# Uebungsboard2017.net
KiCad netlist of a schematic drawn in EAGLE
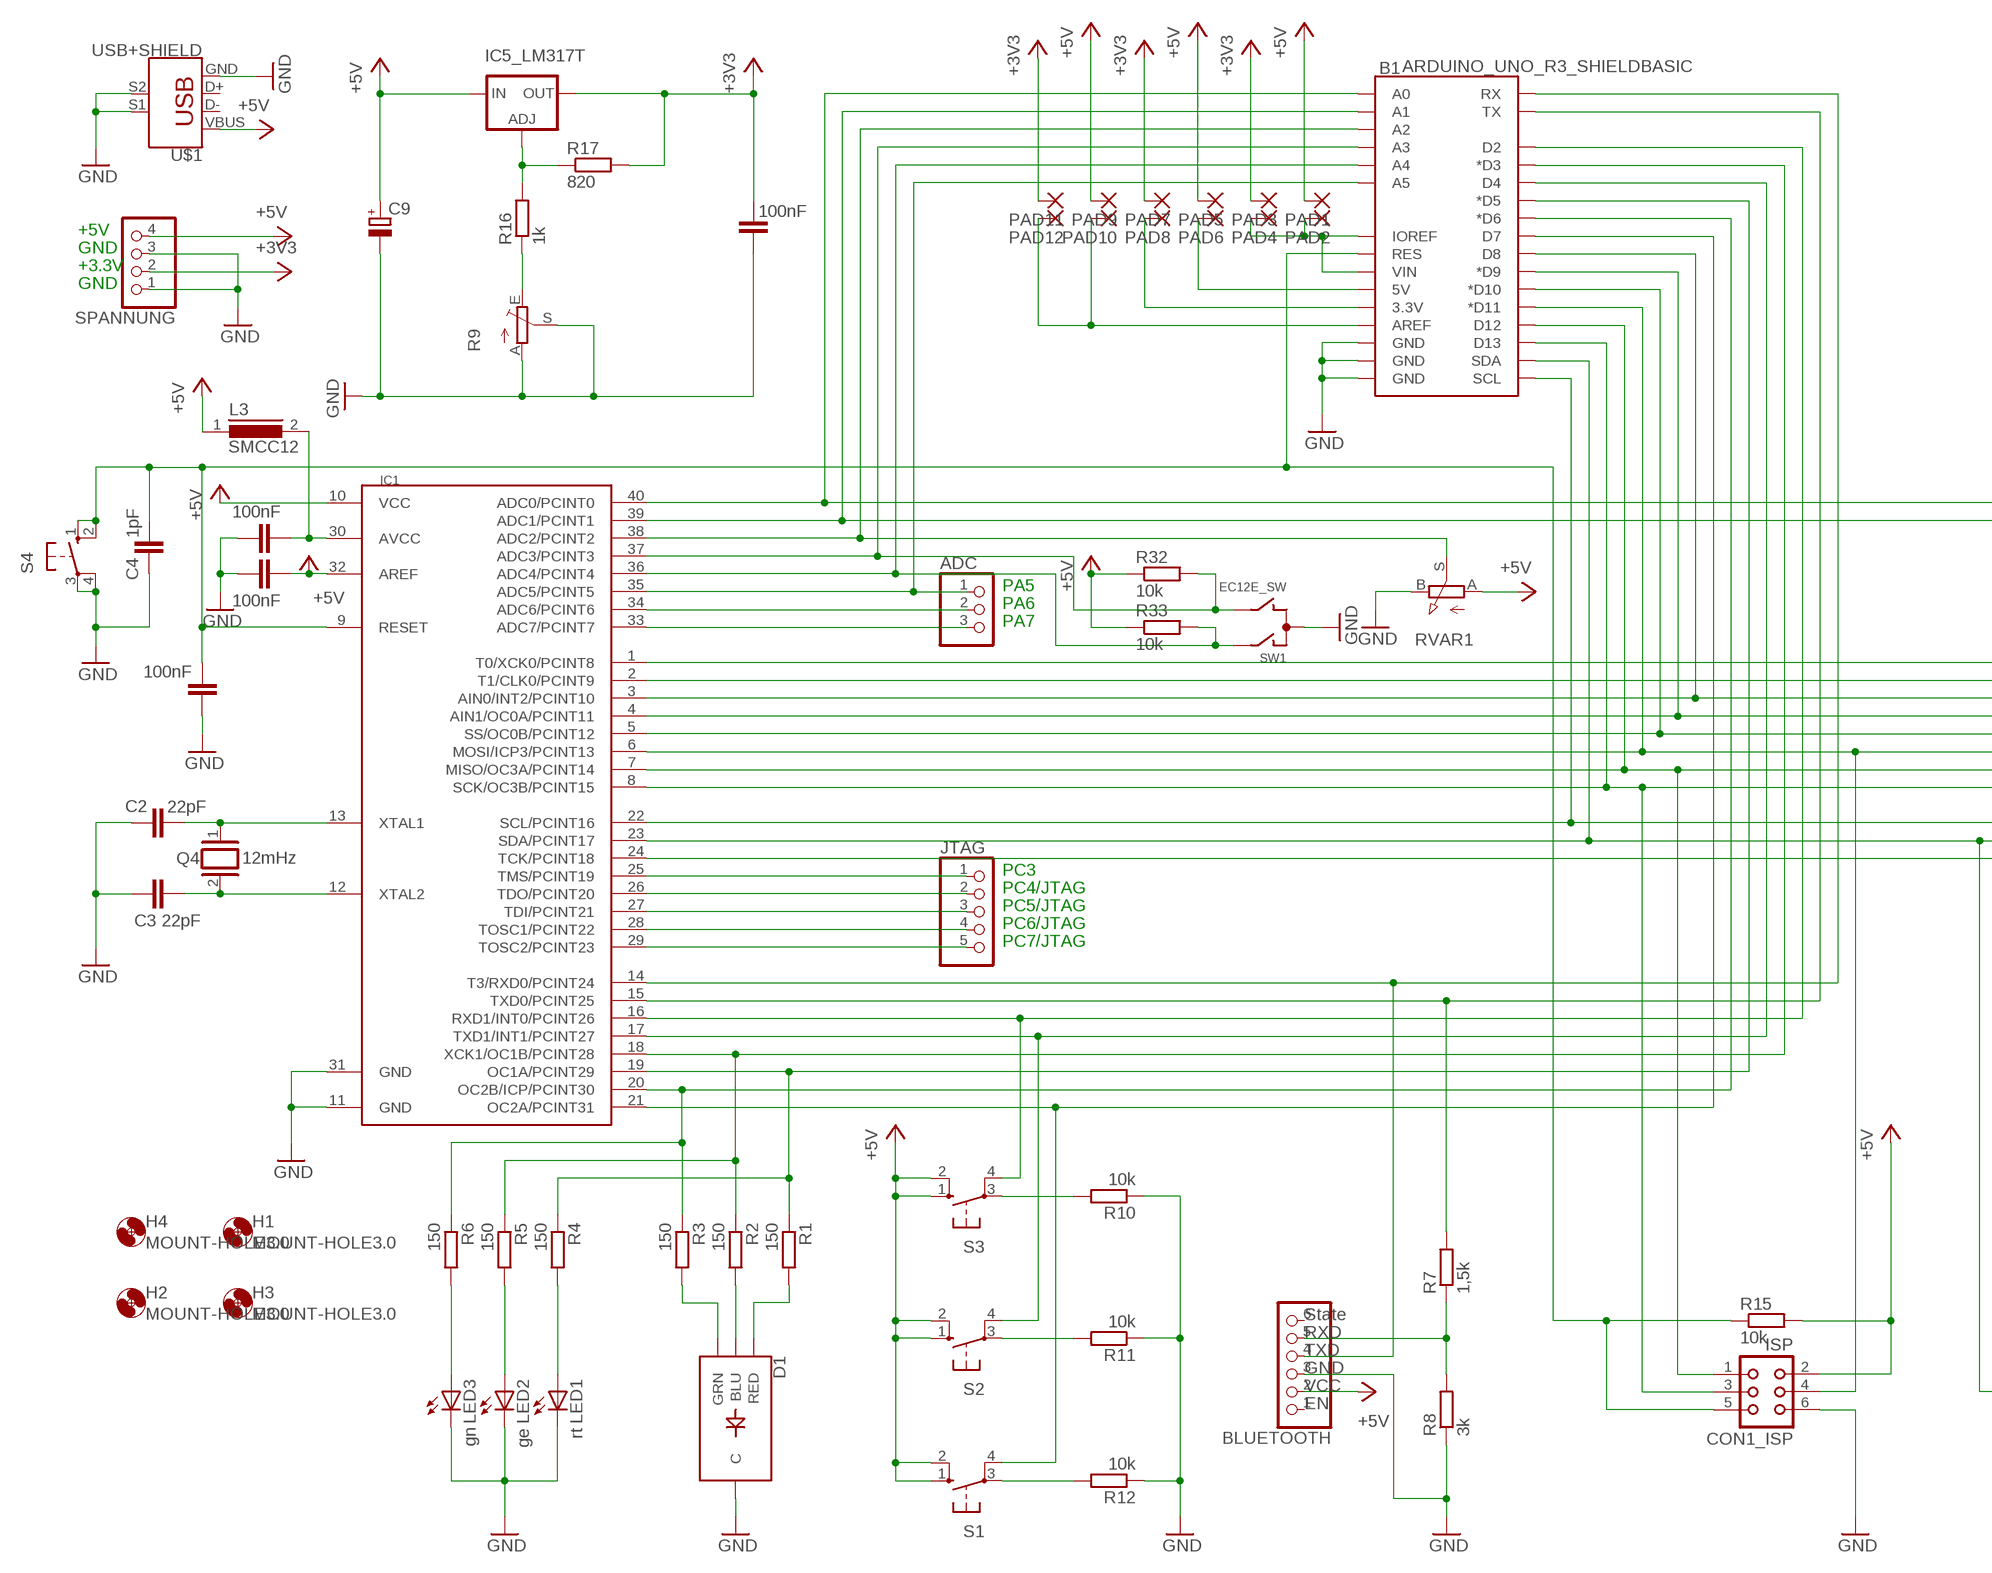
[diagram p0: schematic, sheet 1, part 1 of 2]
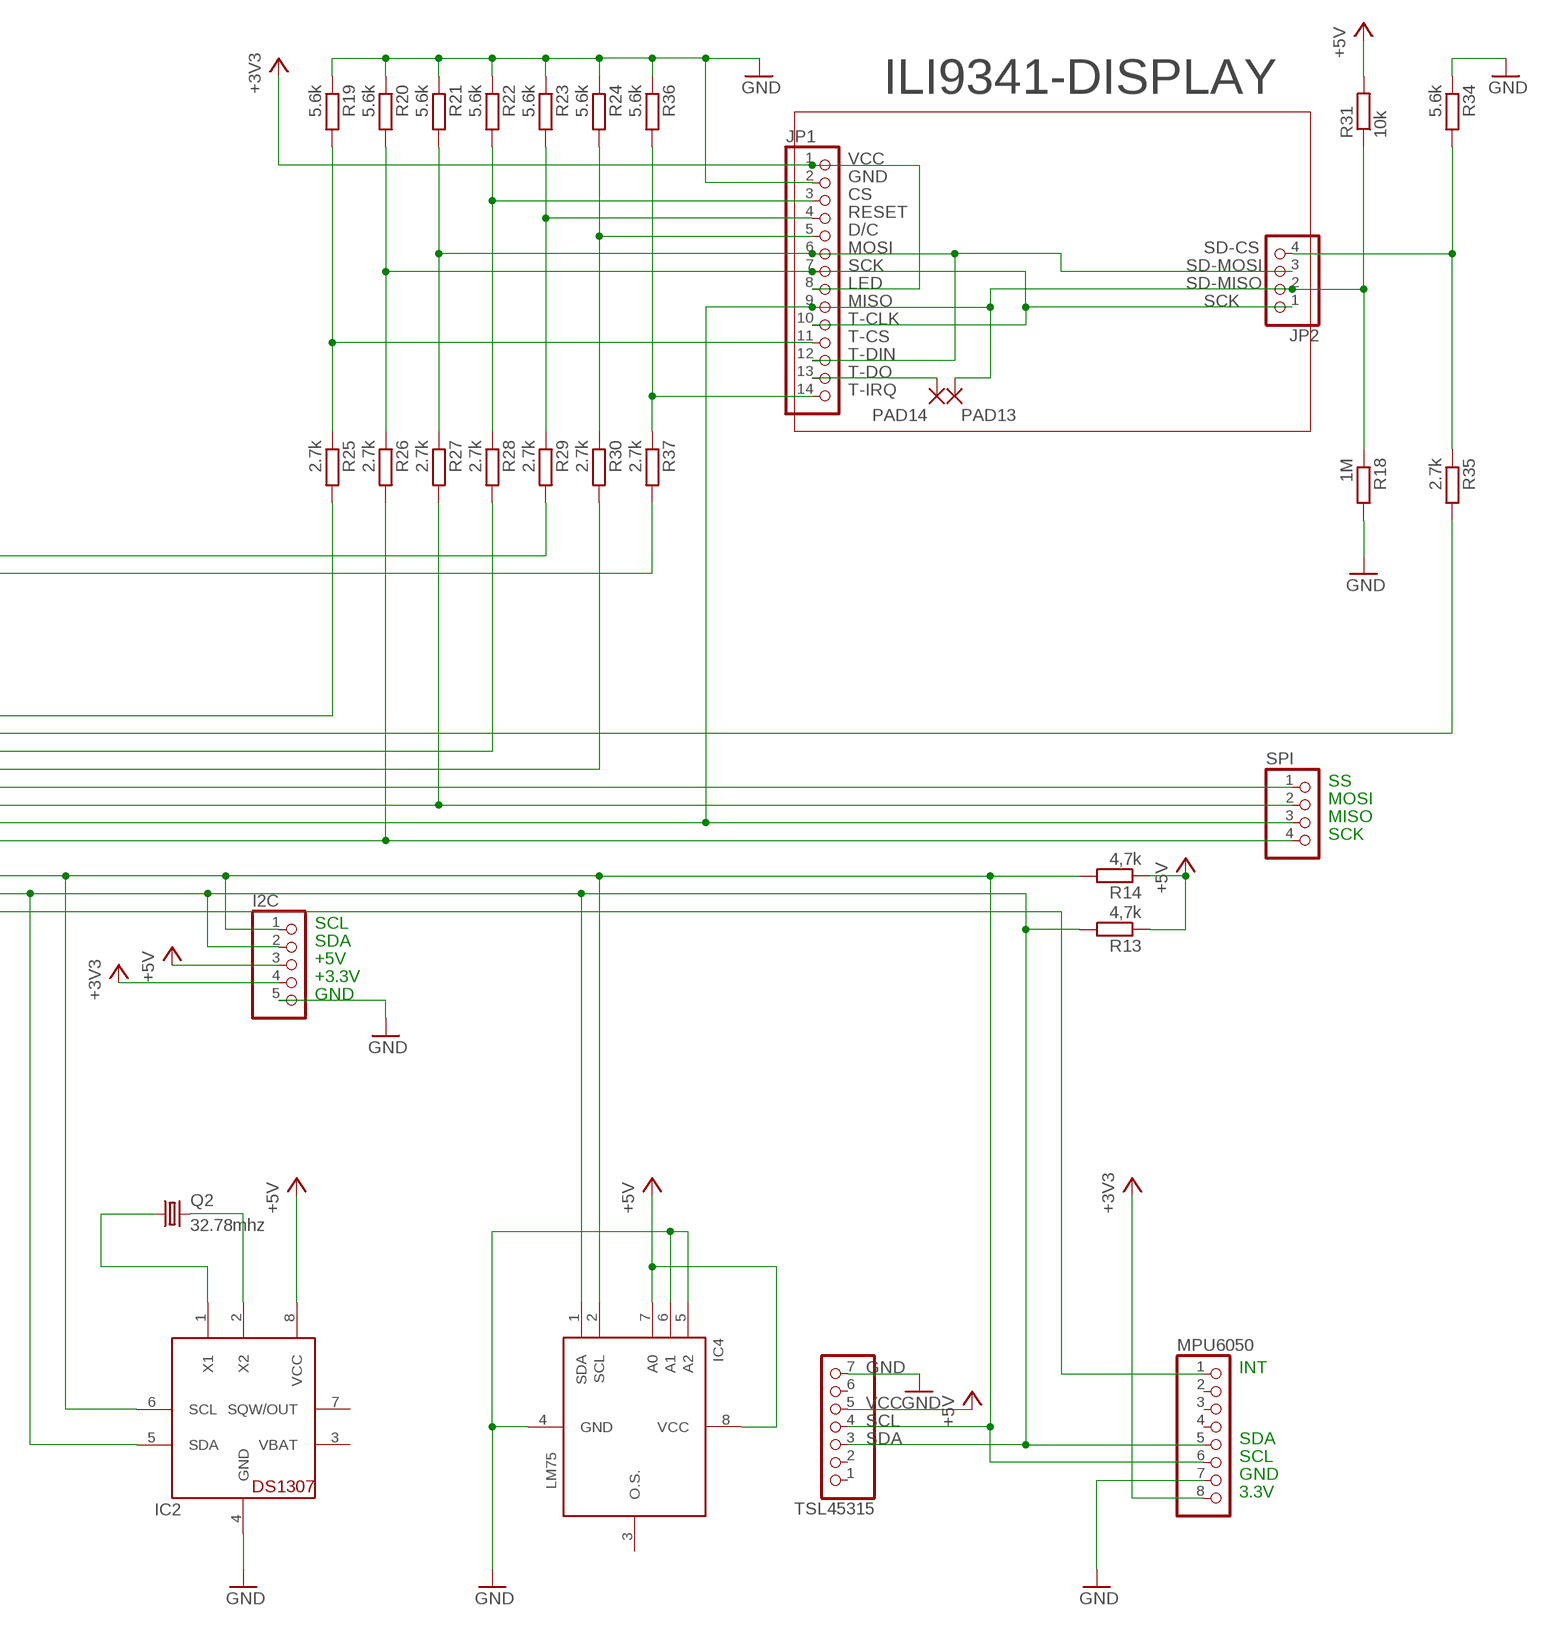
[diagram p1: schematic, sheet 1, part 2 of 2]

(export (version "E")
  (design (tool "Eeschema 10.0.6"))
  (components
    (comp (ref "ADC")
      (value "PINHD-1X3")
      (footprint "eagle-import:1X03")
      (libsource (lib "eagle-import") (part "PINHD-1X3"))
    )
    (comp (ref "B1")
      (value "ARDUINO_UNO_R3_SHIELDBASIC")
      (footprint "eagle-import:UNO_R3_SHIELD")
      (libsource (lib "eagle-import") (part "ARDUINO_UNO_R3_SHIELDBASIC"))
    )
    (comp (ref "BLUETOOTH")
      (value "PINHD-1X6")
      (footprint "eagle-import:1X06")
      (libsource (lib "eagle-import") (part "PINHD-1X6"))
    )
    (comp (ref "C2")
      (value "22pF")
      (footprint "eagle-import:C5B2.5")
      (libsource (lib "eagle-import") (part "C5/2.5"))
    )
    (comp (ref "C3")
      (value "22pF")
      (footprint "eagle-import:C5B2.5")
      (libsource (lib "eagle-import") (part "C5/2.5"))
    )
    (comp (ref "C4")
      (value "1pF")
      (footprint "eagle-import:C5B2.5")
      (libsource (lib "eagle-import") (part "C5/2.5"))
    )
    (comp (ref "C5")
      (value "100nF")
      (footprint "eagle-import:C5B2.5")
      (libsource (lib "eagle-import") (part "C5/2.5"))
    )
    (comp (ref "C6")
      (value "100nF")
      (footprint "eagle-import:C5B2.5")
      (libsource (lib "eagle-import") (part "C5/2.5"))
    )
    (comp (ref "C7")
      (value "100nF")
      (footprint "eagle-import:C5B2.5")
      (libsource (lib "eagle-import") (part "C5/2.5"))
    )
    (comp (ref "C8")
      (value "100nF")
      (footprint "eagle-import:C5B2.5")
      (libsource (lib "eagle-import") (part "C5/2.5"))
    )
    (comp (ref "C9")
      (value "CPOL-EUE2-5")
      (footprint "eagle-import:E2-5")
      (libsource (lib "eagle-import") (part "CPOL-EUE2-5"))
    )
    (comp (ref "CON1_ISP")
      (value "ISP")
      (footprint "eagle-import:CON06")
      (libsource (lib "eagle-import") (part "CON06"))
    )
    (comp (ref "D1")
      (value "LED-RGB-CCTEST")
      (footprint "eagle-import:LED-RGB-THRU")
      (libsource (lib "eagle-import") (part "LED-RGB-CCTEST"))
    )
    (comp (ref "H1")
      (value "MOUNT-HOLE3.0")
      (footprint "eagle-import:3,0")
      (libsource (lib "eagle-import") (part "MOUNT-HOLE3.0"))
    )
    (comp (ref "H2")
      (value "MOUNT-HOLE3.0")
      (footprint "eagle-import:3,0")
      (libsource (lib "eagle-import") (part "MOUNT-HOLE3.0"))
    )
    (comp (ref "H3")
      (value "MOUNT-HOLE3.0")
      (footprint "eagle-import:3,0")
      (libsource (lib "eagle-import") (part "MOUNT-HOLE3.0"))
    )
    (comp (ref "H4")
      (value "MOUNT-HOLE3.0")
      (footprint "eagle-import:3,0")
      (libsource (lib "eagle-import") (part "MOUNT-HOLE3.0"))
    )
    (comp (ref "I2C")
      (value "PINHD-1X5")
      (footprint "eagle-import:1X05")
      (libsource (lib "eagle-import") (part "PINHD-1X5"))
    )
    (comp (ref "IC1")
      (value "MEGA1284P")
      (footprint "eagle-import:DIL40")
      (libsource (lib "eagle-import") (part "MEGA1284P"))
    )
    (comp (ref "IC2")
      (value "DS1307")
      (footprint "eagle-import:DIL08")
      (libsource (lib "eagle-import") (part "DS1307"))
    )
    (comp (ref "IC4")
      (value "DS1721S")
      (footprint "eagle-import:SO-8")
      (libsource (lib "eagle-import") (part "DS1721S"))
    )
    (comp (ref "IC5_LM317T")
      (value "3.3V")
      (footprint "eagle-import:317TS")
      (libsource (lib "eagle-import") (part "LM317TS"))
    )
    (comp (ref "JP1")
      (value "PINHD-1X14")
      (footprint "eagle-import:1X14")
      (libsource (lib "eagle-import") (part "PINHD-1X14"))
    )
    (comp (ref "JP2")
      (value "PINHD-1X4")
      (footprint "eagle-import:1X04")
      (libsource (lib "eagle-import") (part "PINHD-1X4"))
    )
    (comp (ref "JTAG")
      (value "PINHD-1X5")
      (footprint "eagle-import:1X05")
      (libsource (lib "eagle-import") (part "PINHD-1X5"))
    )
    (comp (ref "L3")
      (value "SMCC12")
      (footprint "eagle-import:SMCC12")
      (libsource (lib "eagle-import") (part "SMCC12"))
    )
    (comp (ref "LED1")
      (value "rt")
      (footprint "eagle-import:LED5MM")
      (libsource (lib "eagle-import") (part "LED5MM"))
    )
    (comp (ref "LED2")
      (value "ge")
      (footprint "eagle-import:LED5MM")
      (libsource (lib "eagle-import") (part "LED5MM"))
    )
    (comp (ref "LED3")
      (value "gn")
      (footprint "eagle-import:LED5MM")
      (libsource (lib "eagle-import") (part "LED5MM"))
    )
    (comp (ref "MPU6050")
      (value "PINHD-1X8")
      (footprint "eagle-import:1X08")
      (libsource (lib "eagle-import") (part "PINHD-1X8"))
    )
    (comp (ref "PAD1")
      (value "1,6/0,8")
      (footprint "eagle-import:1,6_0,8")
      (libsource (lib "eagle-import") (part "1,6/0,8"))
    )
    (comp (ref "PAD2")
      (value "1,6/0,8")
      (footprint "eagle-import:1,6_0,8")
      (libsource (lib "eagle-import") (part "1,6/0,8"))
    )
    (comp (ref "PAD3")
      (value "1,6/0,8")
      (footprint "eagle-import:1,6_0,8")
      (libsource (lib "eagle-import") (part "1,6/0,8"))
    )
    (comp (ref "PAD4")
      (value "1,6/0,8")
      (footprint "eagle-import:1,6_0,8")
      (libsource (lib "eagle-import") (part "1,6/0,8"))
    )
    (comp (ref "PAD5")
      (value "1,6/0,8")
      (footprint "eagle-import:1,6_0,8")
      (libsource (lib "eagle-import") (part "1,6/0,8"))
    )
    (comp (ref "PAD6")
      (value "1,6/0,8")
      (footprint "eagle-import:1,6_0,8")
      (libsource (lib "eagle-import") (part "1,6/0,8"))
    )
    (comp (ref "PAD7")
      (value "1,6/0,8")
      (footprint "eagle-import:1,6_0,8")
      (libsource (lib "eagle-import") (part "1,6/0,8"))
    )
    (comp (ref "PAD8")
      (value "1,6/0,8")
      (footprint "eagle-import:1,6_0,8")
      (libsource (lib "eagle-import") (part "1,6/0,8"))
    )
    (comp (ref "PAD9")
      (value "1,6/0,8")
      (footprint "eagle-import:1,6_0,8")
      (libsource (lib "eagle-import") (part "1,6/0,8"))
    )
    (comp (ref "PAD10")
      (value "1,6/0,8")
      (footprint "eagle-import:1,6_0,8")
      (libsource (lib "eagle-import") (part "1,6/0,8"))
    )
    (comp (ref "PAD11")
      (value "1,6/0,8")
      (footprint "eagle-import:1,6_0,8")
      (libsource (lib "eagle-import") (part "1,6/0,8"))
    )
    (comp (ref "PAD12")
      (value "1,6/0,8")
      (footprint "eagle-import:1,6_0,8")
      (libsource (lib "eagle-import") (part "1,6/0,8"))
    )
    (comp (ref "PAD13")
      (value "1,6/0,8")
      (footprint "eagle-import:1,6_0,8")
      (libsource (lib "eagle-import") (part "1,6/0,8"))
    )
    (comp (ref "PAD14")
      (value "1,6/0,8")
      (footprint "eagle-import:1,6_0,8")
      (libsource (lib "eagle-import") (part "1,6/0,8"))
    )
    (comp (ref "Q2")
      (value "32.78mhz")
      (footprint "eagle-import:TC26H")
      (libsource (lib "eagle-import") (part "CRYSTALTC26H"))
    )
    (comp (ref "Q4")
      (value "12mHz")
      (footprint "eagle-import:QS")
      (libsource (lib "eagle-import") (part "XTAL/S"))
    )
    (comp (ref "R1")
      (value "150")
      (footprint "eagle-import:0207_10")
      (libsource (lib "eagle-import") (part "R-EU_0207/10"))
    )
    (comp (ref "R2")
      (value "150")
      (footprint "eagle-import:0207_10")
      (libsource (lib "eagle-import") (part "R-EU_0207/10"))
    )
    (comp (ref "R3")
      (value "150")
      (footprint "eagle-import:0207_10")
      (libsource (lib "eagle-import") (part "R-EU_0207/10"))
    )
    (comp (ref "R4")
      (value "150")
      (footprint "eagle-import:0207_10")
      (libsource (lib "eagle-import") (part "R-EU_0207/10"))
    )
    (comp (ref "R5")
      (value "150")
      (footprint "eagle-import:0207_10")
      (libsource (lib "eagle-import") (part "R-EU_0207/10"))
    )
    (comp (ref "R6")
      (value "150")
      (footprint "eagle-import:0207_10")
      (libsource (lib "eagle-import") (part "R-EU_0207/10"))
    )
    (comp (ref "R7")
      (value "1,5k")
      (footprint "eagle-import:0207_10")
      (libsource (lib "eagle-import") (part "R-EU_0207/10"))
    )
    (comp (ref "R8")
      (value "3k")
      (footprint "eagle-import:0207_10")
      (libsource (lib "eagle-import") (part "R-EU_0207/10"))
    )
    (comp (ref "R9")
      (value "TRIM_EU-S63P")
      (footprint "eagle-import:S63P")
      (libsource (lib "eagle-import") (part "TRIM_EU-S63P"))
    )
    (comp (ref "R10")
      (value "10k")
      (footprint "eagle-import:0207_10")
      (libsource (lib "eagle-import") (part "R-EU_0207/10"))
    )
    (comp (ref "R11")
      (value "10k")
      (footprint "eagle-import:0207_10")
      (libsource (lib "eagle-import") (part "R-EU_0207/10"))
    )
    (comp (ref "R12")
      (value "10k")
      (footprint "eagle-import:0207_10")
      (libsource (lib "eagle-import") (part "R-EU_0207/10"))
    )
    (comp (ref "R13")
      (value "4,7k")
      (footprint "eagle-import:0207_10")
      (libsource (lib "eagle-import") (part "R-EU_0207/10"))
    )
    (comp (ref "R14")
      (value "4,7k")
      (footprint "eagle-import:0207_10")
      (libsource (lib "eagle-import") (part "R-EU_0207/10"))
    )
    (comp (ref "R15")
      (value "10k")
      (footprint "eagle-import:0207_10")
      (libsource (lib "eagle-import") (part "R-EU_0207/10"))
    )
    (comp (ref "R16")
      (value "1k")
      (footprint "eagle-import:0207_10")
      (libsource (lib "eagle-import") (part "R-EU_0207/10"))
    )
    (comp (ref "R17")
      (value "820")
      (footprint "eagle-import:0207_10")
      (libsource (lib "eagle-import") (part "R-EU_0207/10"))
    )
    (comp (ref "R18")
      (value "1M")
      (footprint "eagle-import:0207_10")
      (libsource (lib "eagle-import") (part "R-EU_0207/10"))
    )
    (comp (ref "R19")
      (value "5.6k")
      (footprint "eagle-import:0207_10")
      (libsource (lib "eagle-import") (part "R-EU_0207/10"))
    )
    (comp (ref "R20")
      (value "5.6k")
      (footprint "eagle-import:0207_10")
      (libsource (lib "eagle-import") (part "R-EU_0207/10"))
    )
    (comp (ref "R21")
      (value "5.6k")
      (footprint "eagle-import:0207_10")
      (libsource (lib "eagle-import") (part "R-EU_0207/10"))
    )
    (comp (ref "R22")
      (value "5.6k")
      (footprint "eagle-import:0207_10")
      (libsource (lib "eagle-import") (part "R-EU_0207/10"))
    )
    (comp (ref "R23")
      (value "5.6k")
      (footprint "eagle-import:0207_10")
      (libsource (lib "eagle-import") (part "R-EU_0207/10"))
    )
    (comp (ref "R24")
      (value "5.6k")
      (footprint "eagle-import:0207_10")
      (libsource (lib "eagle-import") (part "R-EU_0207/10"))
    )
    (comp (ref "R25")
      (value "2.7k")
      (footprint "eagle-import:0207_10")
      (libsource (lib "eagle-import") (part "R-EU_0207/10"))
    )
    (comp (ref "R26")
      (value "2.7k")
      (footprint "eagle-import:0207_10")
      (libsource (lib "eagle-import") (part "R-EU_0207/10"))
    )
    (comp (ref "R27")
      (value "2.7k")
      (footprint "eagle-import:0207_10")
      (libsource (lib "eagle-import") (part "R-EU_0207/10"))
    )
    (comp (ref "R28")
      (value "2.7k")
      (footprint "eagle-import:0207_10")
      (libsource (lib "eagle-import") (part "R-EU_0207/10"))
    )
    (comp (ref "R29")
      (value "2.7k")
      (footprint "eagle-import:0207_10")
      (libsource (lib "eagle-import") (part "R-EU_0207/10"))
    )
    (comp (ref "R30")
      (value "2.7k")
      (footprint "eagle-import:0207_10")
      (libsource (lib "eagle-import") (part "R-EU_0207/10"))
    )
    (comp (ref "R31")
      (value "10k")
      (footprint "eagle-import:0207_10")
      (libsource (lib "eagle-import") (part "R-EU_0207/10"))
    )
    (comp (ref "R32")
      (value "10k")
      (footprint "eagle-import:0207_10")
      (libsource (lib "eagle-import") (part "R-EU_0207/10"))
    )
    (comp (ref "R33")
      (value "10k")
      (footprint "eagle-import:0207_10")
      (libsource (lib "eagle-import") (part "R-EU_0207/10"))
    )
    (comp (ref "R34")
      (value "5.6k")
      (footprint "eagle-import:0207_10")
      (libsource (lib "eagle-import") (part "R-EU_0207/10"))
    )
    (comp (ref "R35")
      (value "2.7k")
      (footprint "eagle-import:0207_10")
      (libsource (lib "eagle-import") (part "R-EU_0207/10"))
    )
    (comp (ref "R36")
      (value "5.6k")
      (footprint "eagle-import:0207_10")
      (libsource (lib "eagle-import") (part "R-EU_0207/10"))
    )
    (comp (ref "R37")
      (value "2.7k")
      (footprint "eagle-import:0207_10")
      (libsource (lib "eagle-import") (part "R-EU_0207/10"))
    )
    (comp (ref "RVAR1")
      (value "RK09K113")
      (footprint "eagle-import:RK09K113")
      (libsource (lib "eagle-import") (part "RK09K113"))
    )
    (comp (ref "S1")
      (value "10-XX")
      (footprint "eagle-import:B3F-10XX")
      (fields (field (name "MPN") "B3F-1000"))
      (libsource (lib "eagle-import") (part "10-XX"))
    )
    (comp (ref "S2")
      (value "10-XX")
      (footprint "eagle-import:B3F-10XX")
      (fields (field (name "MPN") "B3F-1000"))
      (libsource (lib "eagle-import") (part "10-XX"))
    )
    (comp (ref "S3")
      (value "10-XX")
      (footprint "eagle-import:B3F-10XX")
      (fields (field (name "MPN") "B3F-1000"))
      (libsource (lib "eagle-import") (part "10-XX"))
    )
    (comp (ref "S4")
      (value "10-XX")
      (footprint "eagle-import:B3F-10XX")
      (fields (field (name "MPN") "B3F-1000"))
      (libsource (lib "eagle-import") (part "10-XX"))
    )
    (comp (ref "SPANNUNG")
      (value "PINHD-1X4")
      (footprint "eagle-import:1X04")
      (libsource (lib "eagle-import") (part "PINHD-1X4"))
    )
    (comp (ref "SPI")
      (value "PINHD-1X4")
      (footprint "eagle-import:1X04")
      (libsource (lib "eagle-import") (part "PINHD-1X4"))
    )
    (comp (ref "SW1")
      (value "EC12E_SW")
      (footprint "eagle-import:ALPS_EC12E_SW")
      (fields (field (name "MPN") "EC12E2424407"))
      (libsource (lib "eagle-import") (part "EC12E_SW"))
    )
    (comp (ref "TSL45315")
      (value "PINHD-1X7")
      (footprint "eagle-import:1X07")
      (libsource (lib "eagle-import") (part "PINHD-1X7"))
    )
    (comp (ref "U$1")
      (value "USB+SHIELD")
      (footprint "eagle-import:USB-B-PTH")
      (libsource (lib "eagle-import") (part "USB+SHIELD"))
    )
  )
  (nets
    (net (code "1") (name "+3V3") (class "Default")
      (node (ref "C5") (pin "1") (pinfunction "1_1") (pintype "passive"))
      (node (ref "I2C") (pin "4") (pinfunction "4_4") (pintype "passive"))
      (node (ref "IC5_LM317T") (pin "2") (pinfunction "OUT_2") (pintype "passive"))
      (node (ref "JP1") (pin "1") (pinfunction "1_1") (pintype "passive"))
      (node (ref "JP1") (pin "8") (pinfunction "8_8") (pintype "passive"))
      (node (ref "MPU6050") (pin "8") (pinfunction "8_8") (pintype "passive"))
      (node (ref "PAD11") (pin "1") (pinfunction "P_1") (pintype "passive"))
      (node (ref "PAD3") (pin "1") (pinfunction "P_1") (pintype "passive"))
      (node (ref "PAD7") (pin "1") (pinfunction "P_1") (pintype "passive"))
      (node (ref "R17") (pin "2") (pinfunction "2_2") (pintype "passive"))
      (node (ref "SPANNUNG") (pin "2") (pinfunction "2_2") (pintype "passive"))
    )
    (net (code "2") (name "+5V") (class "Default")
      (node (ref "BLUETOOTH") (pin "2") (pinfunction "2_2") (pintype "passive"))
      (node (ref "C6") (pin "1") (pinfunction "1_1") (pintype "passive"))
      (node (ref "C9") (pin "+") (pinfunction "+_+") (pintype "passive"))
      (node (ref "CON1_ISP") (pin "2") (pinfunction "2_2") (pintype "passive"))
      (node (ref "I2C") (pin "3") (pinfunction "3_3") (pintype "passive"))
      (node (ref "IC1") (pin "10") (pinfunction "VCC_10") (pintype "bidirectional"))
      (node (ref "IC1") (pin "32") (pinfunction "AREF_32") (pintype "bidirectional"))
      (node (ref "IC2") (pin "8") (pinfunction "VCC_8") (pintype "power_in"))
      (node (ref "IC4") (pin "7") (pinfunction "A0_7") (pintype "input"))
      (node (ref "IC4") (pin "8") (pinfunction "VCC_8") (pintype "power_in"))
      (node (ref "IC5_LM317T") (pin "3") (pinfunction "IN_3") (pintype "input"))
      (node (ref "L3") (pin "1") (pinfunction "1_1") (pintype "passive"))
      (node (ref "PAD1") (pin "1") (pinfunction "P_1") (pintype "passive"))
      (node (ref "PAD5") (pin "1") (pinfunction "P_1") (pintype "passive"))
      (node (ref "PAD9") (pin "1") (pinfunction "P_1") (pintype "passive"))
      (node (ref "R13") (pin "1") (pinfunction "1_1") (pintype "passive"))
      (node (ref "R14") (pin "1") (pinfunction "1_1") (pintype "passive"))
      (node (ref "R15") (pin "2") (pinfunction "2_2") (pintype "passive"))
      (node (ref "R31") (pin "2") (pinfunction "2_2") (pintype "passive"))
      (node (ref "R32") (pin "1") (pinfunction "1_1") (pintype "passive"))
      (node (ref "R33") (pin "1") (pinfunction "1_1") (pintype "passive"))
      (node (ref "RVAR1") (pin "A") (pinfunction "A_A") (pintype "passive"))
      (node (ref "S1") (pin "1") (pinfunction "S_1") (pintype "passive"))
      (node (ref "S1") (pin "2") (pinfunction "S1_2") (pintype "passive"))
      (node (ref "S2") (pin "1") (pinfunction "S_1") (pintype "passive"))
      (node (ref "S2") (pin "2") (pinfunction "S1_2") (pintype "passive"))
      (node (ref "S3") (pin "1") (pinfunction "S_1") (pintype "passive"))
      (node (ref "S3") (pin "2") (pinfunction "S1_2") (pintype "passive"))
      (node (ref "SPANNUNG") (pin "4") (pinfunction "4_4") (pintype "passive"))
      (node (ref "TSL45315") (pin "5") (pinfunction "5_5") (pintype "passive"))
      (node (ref "U$1") (pin "VBUS") (pinfunction "VBUS_VBUS") (pintype "power_in"))
    )
    (net (code "3") (name "/VBAT") (class "Default")
      (node (ref "IC2") (pin "3") (pinfunction "VBAT_3") (pintype "power_in"))
    )
    (net (code "4") (name "GND") (class "Default")
      (node (ref "B1") (pin "GND@0") (pinfunction "GND_GND@0") (pintype "bidirectional"))
      (node (ref "B1") (pin "GND@1") (pinfunction "GND_GND@1") (pintype "bidirectional"))
      (node (ref "B1") (pin "GND@2") (pinfunction "GND_GND@2") (pintype "bidirectional"))
      (node (ref "BLUETOOTH") (pin "3") (pinfunction "3_3") (pintype "passive"))
      (node (ref "C2") (pin "2") (pinfunction "2_2") (pintype "passive"))
      (node (ref "C3") (pin "1") (pinfunction "1_1") (pintype "passive"))
      (node (ref "C4") (pin "2") (pinfunction "2_2") (pintype "passive"))
      (node (ref "C5") (pin "2") (pinfunction "2_2") (pintype "passive"))
      (node (ref "C6") (pin "2") (pinfunction "2_2") (pintype "passive"))
      (node (ref "C7") (pin "2") (pinfunction "2_2") (pintype "passive"))
      (node (ref "C8") (pin "2") (pinfunction "2_2") (pintype "passive"))
      (node (ref "C9") (pin "-") (pinfunction "-_-") (pintype "passive"))
      (node (ref "CON1_ISP") (pin "6") (pinfunction "6_6") (pintype "passive"))
      (node (ref "D1") (pin "2") (pinfunction "C_2") (pintype "bidirectional"))
      (node (ref "I2C") (pin "5") (pinfunction "5_5") (pintype "passive"))
      (node (ref "IC1") (pin "11") (pinfunction "GND_11") (pintype "bidirectional"))
      (node (ref "IC1") (pin "31") (pinfunction "GND_31") (pintype "bidirectional"))
      (node (ref "IC2") (pin "4") (pinfunction "GND_4") (pintype "power_in"))
      (node (ref "IC4") (pin "4") (pinfunction "GND_4") (pintype "power_in"))
      (node (ref "IC4") (pin "5") (pinfunction "A2_5") (pintype "input"))
      (node (ref "IC4") (pin "6") (pinfunction "A1_6") (pintype "input"))
      (node (ref "JP1") (pin "2") (pinfunction "2_2") (pintype "passive"))
      (node (ref "LED1") (pin "K") (pinfunction "C_K") (pintype "passive"))
      (node (ref "LED2") (pin "K") (pinfunction "C_K") (pintype "passive"))
      (node (ref "LED3") (pin "K") (pinfunction "C_K") (pintype "passive"))
      (node (ref "MPU6050") (pin "7") (pinfunction "7_7") (pintype "passive"))
      (node (ref "R10") (pin "1") (pinfunction "1_1") (pintype "passive"))
      (node (ref "R11") (pin "1") (pinfunction "1_1") (pintype "passive"))
      (node (ref "R12") (pin "1") (pinfunction "1_1") (pintype "passive"))
      (node (ref "R18") (pin "2") (pinfunction "2_2") (pintype "passive"))
      (node (ref "R19") (pin "1") (pinfunction "1_1") (pintype "passive"))
      (node (ref "R20") (pin "1") (pinfunction "1_1") (pintype "passive"))
      (node (ref "R21") (pin "1") (pinfunction "1_1") (pintype "passive"))
      (node (ref "R22") (pin "1") (pinfunction "1_1") (pintype "passive"))
      (node (ref "R23") (pin "1") (pinfunction "1_1") (pintype "passive"))
      (node (ref "R24") (pin "1") (pinfunction "1_1") (pintype "passive"))
      (node (ref "R34") (pin "1") (pinfunction "1_1") (pintype "passive"))
      (node (ref "R36") (pin "1") (pinfunction "1_1") (pintype "passive"))
      (node (ref "R8") (pin "1") (pinfunction "1_1") (pintype "passive"))
      (node (ref "R9") (pin "A") (pinfunction "A_A") (pintype "passive"))
      (node (ref "R9") (pin "S") (pinfunction "S_S") (pintype "passive"))
      (node (ref "RVAR1") (pin "B") (pinfunction "E_B") (pintype "passive"))
      (node (ref "S4") (pin "3") (pinfunction "P_3") (pintype "passive"))
      (node (ref "S4") (pin "4") (pinfunction "P1_4") (pintype "passive"))
      (node (ref "SPANNUNG") (pin "1") (pinfunction "1_1") (pintype "passive"))
      (node (ref "SPANNUNG") (pin "3") (pinfunction "3_3") (pintype "passive"))
      (node (ref "SW1") (pin "C") (pinfunction "C_C") (pintype "passive"))
      (node (ref "TSL45315") (pin "7") (pinfunction "7_7") (pintype "passive"))
      (node (ref "U$1") (pin "GND") (pinfunction "GND_GND") (pintype "power_in"))
      (node (ref "U$1") (pin "S1") (pinfunction "S1_S1") (pintype "bidirectional"))
      (node (ref "U$1") (pin "S2") (pinfunction "S2_S2") (pintype "bidirectional"))
    )
    (net (code "5") (name "Net-(B1-*D3)") (class "Default")
      (node (ref "B1") (pin "D3") (pinfunction "*D3_D3") (pintype "bidirectional"))
      (node (ref "IC1") (pin "18") (pinfunction "XCK1/OC1B/PCINT28_18") (pintype "bidirectional"))
      (node (ref "R2") (pin "1") (pinfunction "1_1") (pintype "passive"))
      (node (ref "R5") (pin "1") (pinfunction "1_1") (pintype "passive"))
    )
    (net (code "6") (name "Net-(B1-*D5)") (class "Default")
      (node (ref "B1") (pin "D5") (pinfunction "*D5_D5") (pintype "bidirectional"))
      (node (ref "IC1") (pin "19") (pinfunction "OC1A/PCINT29_19") (pintype "bidirectional"))
      (node (ref "R1") (pin "1") (pinfunction "1_1") (pintype "passive"))
      (node (ref "R4") (pin "1") (pinfunction "1_1") (pintype "passive"))
    )
    (net (code "7") (name "Net-(B1-*D6)") (class "Default")
      (node (ref "B1") (pin "D6") (pinfunction "*D6_D6") (pintype "bidirectional"))
      (node (ref "IC1") (pin "20") (pinfunction "OC2B/ICP/PCINT30_20") (pintype "bidirectional"))
      (node (ref "R3") (pin "1") (pinfunction "1_1") (pintype "passive"))
      (node (ref "R6") (pin "1") (pinfunction "1_1") (pintype "passive"))
    )
    (net (code "8") (name "Net-(B1-*D9)") (class "Default")
      (node (ref "B1") (pin "D9") (pinfunction "*D9_D9") (pintype "bidirectional"))
      (node (ref "IC1") (pin "4") (pinfunction "AIN1/OC0A/PCINT11_4") (pintype "bidirectional"))
      (node (ref "R30") (pin "2") (pinfunction "2_2") (pintype "passive"))
    )
    (net (code "9") (name "Net-(B1-*D10)") (class "Default")
      (node (ref "B1") (pin "D10") (pinfunction "*D10_D10") (pintype "bidirectional"))
      (node (ref "IC1") (pin "5") (pinfunction "SS/OC0B/PCINT12_5") (pintype "bidirectional"))
      (node (ref "SPI") (pin "1") (pinfunction "1_1") (pintype "passive"))
    )
    (net (code "10") (name "Net-(B1-*D11)") (class "Default")
      (node (ref "B1") (pin "D11") (pinfunction "*D11_D11") (pintype "bidirectional"))
      (node (ref "CON1_ISP") (pin "4") (pinfunction "4_4") (pintype "passive"))
      (node (ref "IC1") (pin "6") (pinfunction "MOSI/ICP3/PCINT13_6") (pintype "bidirectional"))
      (node (ref "R27") (pin "2") (pinfunction "2_2") (pintype "passive"))
      (node (ref "SPI") (pin "2") (pinfunction "2_2") (pintype "passive"))
    )
    (net (code "11") (name "Net-(BLUETOOTH-Pad5)") (class "Default")
      (node (ref "BLUETOOTH") (pin "5") (pinfunction "5_5") (pintype "passive"))
      (node (ref "R7") (pin "1") (pinfunction "1_1") (pintype "passive"))
      (node (ref "R8") (pin "2") (pinfunction "2_2") (pintype "passive"))
    )
    (net (code "12") (name "Net-(D1-BLU)") (class "Default")
      (node (ref "D1") (pin "4") (pinfunction "BLU_4") (pintype "bidirectional"))
      (node (ref "R2") (pin "2") (pinfunction "2_2") (pintype "passive"))
    )
    (net (code "13") (name "Net-(D1-GRN)") (class "Default")
      (node (ref "D1") (pin "3") (pinfunction "GRN_3") (pintype "bidirectional"))
      (node (ref "R3") (pin "2") (pinfunction "2_2") (pintype "passive"))
    )
    (net (code "14") (name "Net-(D1-RED)") (class "Default")
      (node (ref "D1") (pin "1") (pinfunction "RED_1") (pintype "bidirectional"))
      (node (ref "R1") (pin "2") (pinfunction "2_2") (pintype "passive"))
    )
    (net (code "15") (name "Net-(IC1-ADC0{slash}PCINT0)") (class "Default")
      (node (ref "B1") (pin "A0") (pinfunction "A0_A0") (pintype "bidirectional"))
      (node (ref "IC1") (pin "40") (pinfunction "ADC0/PCINT0_40") (pintype "bidirectional"))
      (node (ref "R29") (pin "2") (pinfunction "2_2") (pintype "passive"))
    )
    (net (code "16") (name "Net-(IC1-ADC1{slash}PCINT1)") (class "Default")
      (node (ref "B1") (pin "A1") (pinfunction "A1_A1") (pintype "bidirectional"))
      (node (ref "IC1") (pin "39") (pinfunction "ADC1/PCINT1_39") (pintype "bidirectional"))
      (node (ref "R37") (pin "2") (pinfunction "2_2") (pintype "passive"))
    )
    (net (code "17") (name "Net-(IC1-ADC2{slash}PCINT2)") (class "Default")
      (node (ref "B1") (pin "A2") (pinfunction "A2_A2") (pintype "bidirectional"))
      (node (ref "IC1") (pin "38") (pinfunction "ADC2/PCINT2_38") (pintype "bidirectional"))
      (node (ref "RVAR1") (pin "S") (pinfunction "S_S") (pintype "passive"))
    )
    (net (code "18") (name "Net-(IC1-ADC3{slash}PCINT3)") (class "Default")
      (node (ref "B1") (pin "A3") (pinfunction "A3_A3") (pintype "bidirectional"))
      (node (ref "IC1") (pin "37") (pinfunction "ADC3/PCINT3_37") (pintype "bidirectional"))
      (node (ref "R32") (pin "2") (pinfunction "2_2") (pintype "passive"))
      (node (ref "SW1") (pin "B") (pinfunction "B_B") (pintype "passive"))
    )
    (net (code "19") (name "Net-(IC1-ADC4{slash}PCINT4)") (class "Default")
      (node (ref "B1") (pin "A4") (pinfunction "A4_A4") (pintype "bidirectional"))
      (node (ref "IC1") (pin "36") (pinfunction "ADC4/PCINT4_36") (pintype "bidirectional"))
      (node (ref "R33") (pin "2") (pinfunction "2_2") (pintype "passive"))
      (node (ref "SW1") (pin "A") (pinfunction "A_A") (pintype "passive"))
    )
    (net (code "20") (name "Net-(IC1-ADC5{slash}PCINT5)") (class "Default")
      (node (ref "ADC") (pin "1") (pinfunction "1_1") (pintype "passive"))
      (node (ref "B1") (pin "A5") (pinfunction "A5_A5") (pintype "bidirectional"))
      (node (ref "IC1") (pin "35") (pinfunction "ADC5/PCINT5_35") (pintype "bidirectional"))
    )
    (net (code "21") (name "Net-(IC1-ADC6{slash}PCINT6)") (class "Default")
      (node (ref "ADC") (pin "2") (pinfunction "2_2") (pintype "passive"))
      (node (ref "IC1") (pin "34") (pinfunction "ADC6/PCINT6_34") (pintype "bidirectional"))
    )
    (net (code "22") (name "Net-(IC1-ADC7{slash}PCINT7)") (class "Default")
      (node (ref "ADC") (pin "3") (pinfunction "3_3") (pintype "passive"))
      (node (ref "IC1") (pin "33") (pinfunction "ADC7/PCINT7_33") (pintype "bidirectional"))
    )
    (net (code "23") (name "Net-(IC1-AIN0{slash}INT2{slash}PCINT10)") (class "Default")
      (node (ref "B1") (pin "D8") (pinfunction "D8_D8") (pintype "bidirectional"))
      (node (ref "IC1") (pin "3") (pinfunction "AIN0/INT2/PCINT10_3") (pintype "bidirectional"))
      (node (ref "R28") (pin "2") (pinfunction "2_2") (pintype "passive"))
    )
    (net (code "24") (name "Net-(IC1-AVCC)") (class "Default")
      (node (ref "C7") (pin "1") (pinfunction "1_1") (pintype "passive"))
      (node (ref "IC1") (pin "30") (pinfunction "AVCC_30") (pintype "bidirectional"))
      (node (ref "L3") (pin "2") (pinfunction "2_2") (pintype "passive"))
    )
    (net (code "25") (name "Net-(IC1-MISO{slash}OC3A{slash}PCINT14)") (class "Default")
      (node (ref "B1") (pin "D12") (pinfunction "D12_D12") (pintype "bidirectional"))
      (node (ref "CON1_ISP") (pin "1") (pinfunction "1_1") (pintype "passive"))
      (node (ref "IC1") (pin "7") (pinfunction "MISO/OC3A/PCINT14_7") (pintype "bidirectional"))
      (node (ref "JP1") (pin "9") (pinfunction "9_9") (pintype "passive"))
      (node (ref "JP2") (pin "2") (pinfunction "2_2") (pintype "passive"))
      (node (ref "PAD13") (pin "1") (pinfunction "P_1") (pintype "passive"))
      (node (ref "R18") (pin "1") (pinfunction "1_1") (pintype "passive"))
      (node (ref "R31") (pin "1") (pinfunction "1_1") (pintype "passive"))
      (node (ref "SPI") (pin "3") (pinfunction "3_3") (pintype "passive"))
    )
    (net (code "26") (name "Net-(IC1-OC2A{slash}PCINT31)") (class "Default")
      (node (ref "B1") (pin "D7") (pinfunction "D7_D7") (pintype "bidirectional"))
      (node (ref "IC1") (pin "21") (pinfunction "OC2A/PCINT31_21") (pintype "bidirectional"))
      (node (ref "S1") (pin "4") (pinfunction "P1_4") (pintype "passive"))
    )
    (net (code "27") (name "Net-(IC1-RESET)") (class "Default")
      (node (ref "B1") (pin "RES") (pinfunction "RES_RES") (pintype "bidirectional"))
      (node (ref "C4") (pin "1") (pinfunction "1_1") (pintype "passive"))
      (node (ref "C8") (pin "1") (pinfunction "1_1") (pintype "passive"))
      (node (ref "CON1_ISP") (pin "5") (pinfunction "5_5") (pintype "passive"))
      (node (ref "IC1") (pin "9") (pinfunction "RESET_9") (pintype "bidirectional"))
      (node (ref "R15") (pin "1") (pinfunction "1_1") (pintype "passive"))
      (node (ref "S4") (pin "1") (pinfunction "S_1") (pintype "passive"))
      (node (ref "S4") (pin "2") (pinfunction "S1_2") (pintype "passive"))
    )
    (net (code "28") (name "Net-(IC1-RXD1{slash}INT0{slash}PCINT26)") (class "Default")
      (node (ref "B1") (pin "D2") (pinfunction "D2_D2") (pintype "bidirectional"))
      (node (ref "IC1") (pin "16") (pinfunction "RXD1/INT0/PCINT26_16") (pintype "bidirectional"))
      (node (ref "S3") (pin "4") (pinfunction "P1_4") (pintype "passive"))
    )
    (net (code "29") (name "Net-(IC1-SCK{slash}OC3B{slash}PCINT15)") (class "Default")
      (node (ref "B1") (pin "D13") (pinfunction "D13_D13") (pintype "bidirectional"))
      (node (ref "CON1_ISP") (pin "3") (pinfunction "3_3") (pintype "passive"))
      (node (ref "IC1") (pin "8") (pinfunction "SCK/OC3B/PCINT15_8") (pintype "bidirectional"))
      (node (ref "R26") (pin "2") (pinfunction "2_2") (pintype "passive"))
      (node (ref "SPI") (pin "4") (pinfunction "4_4") (pintype "passive"))
    )
    (net (code "30") (name "Net-(IC1-SCL{slash}PCINT16)") (class "Default")
      (node (ref "B1") (pin "SCL") (pinfunction "SCL_SCL") (pintype "bidirectional"))
      (node (ref "I2C") (pin "1") (pinfunction "1_1") (pintype "passive"))
      (node (ref "IC1") (pin "22") (pinfunction "SCL/PCINT16_22") (pintype "bidirectional"))
      (node (ref "IC2") (pin "6") (pinfunction "SCL_6") (pintype "bidirectional"))
      (node (ref "IC4") (pin "2") (pinfunction "SCL_2") (pintype "input"))
      (node (ref "MPU6050") (pin "6") (pinfunction "6_6") (pintype "passive"))
      (node (ref "R14") (pin "2") (pinfunction "2_2") (pintype "passive"))
      (node (ref "TSL45315") (pin "4") (pinfunction "4_4") (pintype "passive"))
    )
    (net (code "31") (name "Net-(IC1-SDA{slash}PCINT17)") (class "Default")
      (node (ref "B1") (pin "SDA") (pinfunction "SDA_SDA") (pintype "bidirectional"))
      (node (ref "I2C") (pin "2") (pinfunction "2_2") (pintype "passive"))
      (node (ref "IC1") (pin "23") (pinfunction "SDA/PCINT17_23") (pintype "bidirectional"))
      (node (ref "IC2") (pin "5") (pinfunction "SDA_5") (pintype "bidirectional"))
      (node (ref "IC4") (pin "1") (pinfunction "SDA_1") (pintype "bidirectional"))
      (node (ref "MPU6050") (pin "5") (pinfunction "5_5") (pintype "passive"))
      (node (ref "R13") (pin "2") (pinfunction "2_2") (pintype "passive"))
      (node (ref "TSL45315") (pin "3") (pinfunction "3_3") (pintype "passive"))
    )
    (net (code "32") (name "Net-(IC1-T0{slash}XCK0{slash}PCINT8)") (class "Default")
      (node (ref "IC1") (pin "1") (pinfunction "T0/XCK0/PCINT8_1") (pintype "bidirectional"))
      (node (ref "R25") (pin "2") (pinfunction "2_2") (pintype "passive"))
    )
    (net (code "33") (name "Net-(IC1-T1{slash}CLK0{slash}PCINT9)") (class "Default")
      (node (ref "IC1") (pin "2") (pinfunction "T1/CLK0/PCINT9_2") (pintype "bidirectional"))
      (node (ref "R35") (pin "2") (pinfunction "2_2") (pintype "passive"))
    )
    (net (code "34") (name "Net-(IC1-T3{slash}RXD0{slash}PCINT24)") (class "Default")
      (node (ref "B1") (pin "RX") (pinfunction "RX_RX") (pintype "bidirectional"))
      (node (ref "BLUETOOTH") (pin "4") (pinfunction "4_4") (pintype "passive"))
      (node (ref "IC1") (pin "14") (pinfunction "T3/RXD0/PCINT24_14") (pintype "bidirectional"))
    )
    (net (code "35") (name "Net-(IC1-TCK{slash}PCINT18)") (class "Default")
      (node (ref "IC1") (pin "24") (pinfunction "TCK/PCINT18_24") (pintype "bidirectional"))
      (node (ref "MPU6050") (pin "1") (pinfunction "1_1") (pintype "passive"))
    )
    (net (code "36") (name "Net-(IC1-TDI{slash}PCINT21)") (class "Default")
      (node (ref "IC1") (pin "27") (pinfunction "TDI/PCINT21_27") (pintype "bidirectional"))
      (node (ref "JTAG") (pin "3") (pinfunction "3_3") (pintype "passive"))
    )
    (net (code "37") (name "Net-(IC1-TDO{slash}PCINT20)") (class "Default")
      (node (ref "IC1") (pin "26") (pinfunction "TDO/PCINT20_26") (pintype "bidirectional"))
      (node (ref "JTAG") (pin "2") (pinfunction "2_2") (pintype "passive"))
    )
    (net (code "38") (name "Net-(IC1-TMS{slash}PCINT19)") (class "Default")
      (node (ref "IC1") (pin "25") (pinfunction "TMS/PCINT19_25") (pintype "bidirectional"))
      (node (ref "JTAG") (pin "1") (pinfunction "1_1") (pintype "passive"))
    )
    (net (code "39") (name "Net-(IC1-TOSC1{slash}PCINT22)") (class "Default")
      (node (ref "IC1") (pin "28") (pinfunction "TOSC1/PCINT22_28") (pintype "bidirectional"))
      (node (ref "JTAG") (pin "4") (pinfunction "4_4") (pintype "passive"))
    )
    (net (code "40") (name "Net-(IC1-TOSC2{slash}PCINT23)") (class "Default")
      (node (ref "IC1") (pin "29") (pinfunction "TOSC2/PCINT23_29") (pintype "bidirectional"))
      (node (ref "JTAG") (pin "5") (pinfunction "5_5") (pintype "passive"))
    )
    (net (code "41") (name "Net-(IC1-TXD0{slash}PCINT25)") (class "Default")
      (node (ref "B1") (pin "TX") (pinfunction "TX_TX") (pintype "bidirectional"))
      (node (ref "IC1") (pin "15") (pinfunction "TXD0/PCINT25_15") (pintype "bidirectional"))
      (node (ref "R7") (pin "2") (pinfunction "2_2") (pintype "passive"))
    )
    (net (code "42") (name "Net-(IC1-TXD1{slash}INT1{slash}PCINT27)") (class "Default")
      (node (ref "B1") (pin "D4") (pinfunction "D4_D4") (pintype "bidirectional"))
      (node (ref "IC1") (pin "17") (pinfunction "TXD1/INT1/PCINT27_17") (pintype "bidirectional"))
      (node (ref "S2") (pin "4") (pinfunction "P1_4") (pintype "passive"))
    )
    (net (code "43") (name "Net-(IC1-XTAL1)") (class "Default")
      (node (ref "C2") (pin "1") (pinfunction "1_1") (pintype "passive"))
      (node (ref "IC1") (pin "13") (pinfunction "XTAL1_13") (pintype "bidirectional"))
      (node (ref "Q4") (pin "1") (pinfunction "1_1") (pintype "passive"))
    )
    (net (code "44") (name "Net-(IC1-XTAL2)") (class "Default")
      (node (ref "C3") (pin "2") (pinfunction "2_2") (pintype "passive"))
      (node (ref "IC1") (pin "12") (pinfunction "XTAL2_12") (pintype "bidirectional"))
      (node (ref "Q4") (pin "2") (pinfunction "2_2") (pintype "passive"))
    )
    (net (code "45") (name "Net-(IC2-X1)") (class "Default")
      (node (ref "IC2") (pin "1") (pinfunction "X1_1") (pintype "passive"))
      (node (ref "Q2") (pin "1") (pinfunction "1_1") (pintype "passive"))
    )
    (net (code "46") (name "Net-(IC2-X2)") (class "Default")
      (node (ref "IC2") (pin "2") (pinfunction "X2_2") (pintype "passive"))
      (node (ref "Q2") (pin "2") (pinfunction "2_2") (pintype "passive"))
    )
    (net (code "47") (name "Net-(IC5_LM317T-ADJ)") (class "Default")
      (node (ref "IC5_LM317T") (pin "1") (pinfunction "ADJ_1") (pintype "input"))
      (node (ref "R16") (pin "2") (pinfunction "2_2") (pintype "passive"))
      (node (ref "R17") (pin "1") (pinfunction "1_1") (pintype "passive"))
    )
    (net (code "48") (name "Net-(JP1-Pad3)") (class "Default")
      (node (ref "JP1") (pin "3") (pinfunction "3_3") (pintype "passive"))
      (node (ref "R22") (pin "2") (pinfunction "2_2") (pintype "passive"))
      (node (ref "R28") (pin "1") (pinfunction "1_1") (pintype "passive"))
    )
    (net (code "49") (name "Net-(JP1-Pad4)") (class "Default")
      (node (ref "JP1") (pin "4") (pinfunction "4_4") (pintype "passive"))
      (node (ref "R23") (pin "2") (pinfunction "2_2") (pintype "passive"))
      (node (ref "R29") (pin "1") (pinfunction "1_1") (pintype "passive"))
    )
    (net (code "50") (name "Net-(JP1-Pad5)") (class "Default")
      (node (ref "JP1") (pin "5") (pinfunction "5_5") (pintype "passive"))
      (node (ref "R24") (pin "2") (pinfunction "2_2") (pintype "passive"))
      (node (ref "R30") (pin "1") (pinfunction "1_1") (pintype "passive"))
    )
    (net (code "51") (name "Net-(JP1-Pad10)") (class "Default")
      (node (ref "JP1") (pin "10") (pinfunction "10_10") (pintype "passive"))
      (node (ref "JP1") (pin "7") (pinfunction "7_7") (pintype "passive"))
      (node (ref "JP2") (pin "1") (pinfunction "1_1") (pintype "passive"))
      (node (ref "R20") (pin "2") (pinfunction "2_2") (pintype "passive"))
      (node (ref "R26") (pin "1") (pinfunction "1_1") (pintype "passive"))
    )
    (net (code "52") (name "Net-(JP1-Pad11)") (class "Default")
      (node (ref "JP1") (pin "11") (pinfunction "11_11") (pintype "passive"))
      (node (ref "R19") (pin "2") (pinfunction "2_2") (pintype "passive"))
      (node (ref "R25") (pin "1") (pinfunction "1_1") (pintype "passive"))
    )
    (net (code "53") (name "Net-(JP1-Pad12)") (class "Default")
      (node (ref "JP1") (pin "12") (pinfunction "12_12") (pintype "passive"))
      (node (ref "JP1") (pin "6") (pinfunction "6_6") (pintype "passive"))
      (node (ref "JP2") (pin "3") (pinfunction "3_3") (pintype "passive"))
      (node (ref "R21") (pin "2") (pinfunction "2_2") (pintype "passive"))
      (node (ref "R27") (pin "1") (pinfunction "1_1") (pintype "passive"))
    )
    (net (code "54") (name "Net-(JP1-Pad14)") (class "Default")
      (node (ref "JP1") (pin "14") (pinfunction "14_14") (pintype "passive"))
      (node (ref "R36") (pin "2") (pinfunction "2_2") (pintype "passive"))
      (node (ref "R37") (pin "1") (pinfunction "1_1") (pintype "passive"))
    )
    (net (code "55") (name "Net-(JP2-Pad4)") (class "Default")
      (node (ref "JP2") (pin "4") (pinfunction "4_4") (pintype "passive"))
      (node (ref "R34") (pin "2") (pinfunction "2_2") (pintype "passive"))
      (node (ref "R35") (pin "1") (pinfunction "1_1") (pintype "passive"))
    )
    (net (code "56") (name "Net-(LED1-PadA)") (class "Default")
      (node (ref "LED1") (pin "A") (pinfunction "A_A") (pintype "passive"))
      (node (ref "R4") (pin "2") (pinfunction "2_2") (pintype "passive"))
    )
    (net (code "57") (name "Net-(LED2-PadA)") (class "Default")
      (node (ref "LED2") (pin "A") (pinfunction "A_A") (pintype "passive"))
      (node (ref "R5") (pin "2") (pinfunction "2_2") (pintype "passive"))
    )
    (net (code "58") (name "Net-(LED3-PadA)") (class "Default")
      (node (ref "LED3") (pin "A") (pinfunction "A_A") (pintype "passive"))
      (node (ref "R6") (pin "2") (pinfunction "2_2") (pintype "passive"))
    )
    (net (code "59") (name "Net-(PAD2-P)") (class "Default")
      (node (ref "B1") (pin "IOREF") (pinfunction "IOREF_IOREF") (pintype "bidirectional"))
      (node (ref "B1") (pin "VIN") (pinfunction "VIN_VIN") (pintype "bidirectional"))
      (node (ref "PAD2") (pin "1") (pinfunction "P_1") (pintype "passive"))
      (node (ref "PAD4") (pin "1") (pinfunction "P_1") (pintype "passive"))
    )
    (net (code "60") (name "Net-(PAD6-P)") (class "Default")
      (node (ref "B1") (pin "5V") (pinfunction "5V_5V") (pintype "bidirectional"))
      (node (ref "PAD6") (pin "1") (pinfunction "P_1") (pintype "passive"))
    )
    (net (code "61") (name "Net-(PAD8-P)") (class "Default")
      (node (ref "B1") (pin "3.3V") (pinfunction "3.3V_3.3V") (pintype "bidirectional"))
      (node (ref "PAD8") (pin "1") (pinfunction "P_1") (pintype "passive"))
    )
    (net (code "62") (name "Net-(PAD10-P)") (class "Default")
      (node (ref "B1") (pin "AREF") (pinfunction "AREF_AREF") (pintype "bidirectional"))
      (node (ref "PAD10") (pin "1") (pinfunction "P_1") (pintype "passive"))
      (node (ref "PAD12") (pin "1") (pinfunction "P_1") (pintype "passive"))
    )
    (net (code "63") (name "Net-(PAD14-P)") (class "Default")
      (node (ref "JP1") (pin "13") (pinfunction "13_13") (pintype "passive"))
      (node (ref "PAD14") (pin "1") (pinfunction "P_1") (pintype "passive"))
    )
    (net (code "64") (name "Net-(R16-Pad1)") (class "Default")
      (node (ref "R16") (pin "1") (pinfunction "1_1") (pintype "passive"))
      (node (ref "R9") (pin "E") (pinfunction "E_E") (pintype "passive"))
    )
    (net (code "65") (name "Net-(S1-P)") (class "Default")
      (node (ref "R12") (pin "2") (pinfunction "2_2") (pintype "passive"))
      (node (ref "S1") (pin "3") (pinfunction "P_3") (pintype "passive"))
    )
    (net (code "66") (name "Net-(S2-P)") (class "Default")
      (node (ref "R11") (pin "2") (pinfunction "2_2") (pintype "passive"))
      (node (ref "S2") (pin "3") (pinfunction "P_3") (pintype "passive"))
    )
    (net (code "67") (name "Net-(S3-P)") (class "Default")
      (node (ref "R10") (pin "2") (pinfunction "2_2") (pintype "passive"))
      (node (ref "S3") (pin "3") (pinfunction "P_3") (pintype "passive"))
    )
    (net (code "68") (name "unconnected-(BLUETOOTH-Pad1)") (class "Default")
      (node (ref "BLUETOOTH") (pin "1") (pinfunction "1_1") (pintype "passive"))
    )
    (net (code "69") (name "unconnected-(BLUETOOTH-Pad6)") (class "Default")
      (node (ref "BLUETOOTH") (pin "6") (pinfunction "6_6") (pintype "passive"))
    )
    (net (code "70") (name "unconnected-(IC2-SQW{slash}OUT-Pad7)") (class "Default")
      (node (ref "IC2") (pin "7") (pinfunction "SQW/OUT_7") (pintype "bidirectional"))
    )
    (net (code "71") (name "unconnected-(IC4-O.S.-Pad3)") (class "Default")
      (node (ref "IC4") (pin "3") (pinfunction "O.S._3") (pintype "output"))
    )
    (net (code "72") (name "unconnected-(MPU6050-Pad2)") (class "Default")
      (node (ref "MPU6050") (pin "2") (pinfunction "2_2") (pintype "passive"))
    )
    (net (code "73") (name "unconnected-(MPU6050-Pad3)") (class "Default")
      (node (ref "MPU6050") (pin "3") (pinfunction "3_3") (pintype "passive"))
    )
    (net (code "74") (name "unconnected-(MPU6050-Pad4)") (class "Default")
      (node (ref "MPU6050") (pin "4") (pinfunction "4_4") (pintype "passive"))
    )
    (net (code "75") (name "unconnected-(TSL45315-Pad1)") (class "Default")
      (node (ref "TSL45315") (pin "1") (pinfunction "1_1") (pintype "passive"))
    )
    (net (code "76") (name "unconnected-(TSL45315-Pad2)") (class "Default")
      (node (ref "TSL45315") (pin "2") (pinfunction "2_2") (pintype "passive"))
    )
    (net (code "77") (name "unconnected-(TSL45315-Pad6)") (class "Default")
      (node (ref "TSL45315") (pin "6") (pinfunction "6_6") (pintype "passive"))
    )
    (net (code "78") (name "unconnected-(U$1-PadD+)") (class "Default")
      (node (ref "U$1") (pin "D+") (pinfunction "D+_D+") (pintype "bidirectional"))
    )
    (net (code "79") (name "unconnected-(U$1-PadD-)") (class "Default")
      (node (ref "U$1") (pin "D-") (pinfunction "D-_D-") (pintype "bidirectional"))
    )
  )
)
